# Atmega328.net
KiCad netlist of a schematic drawn in EAGLE
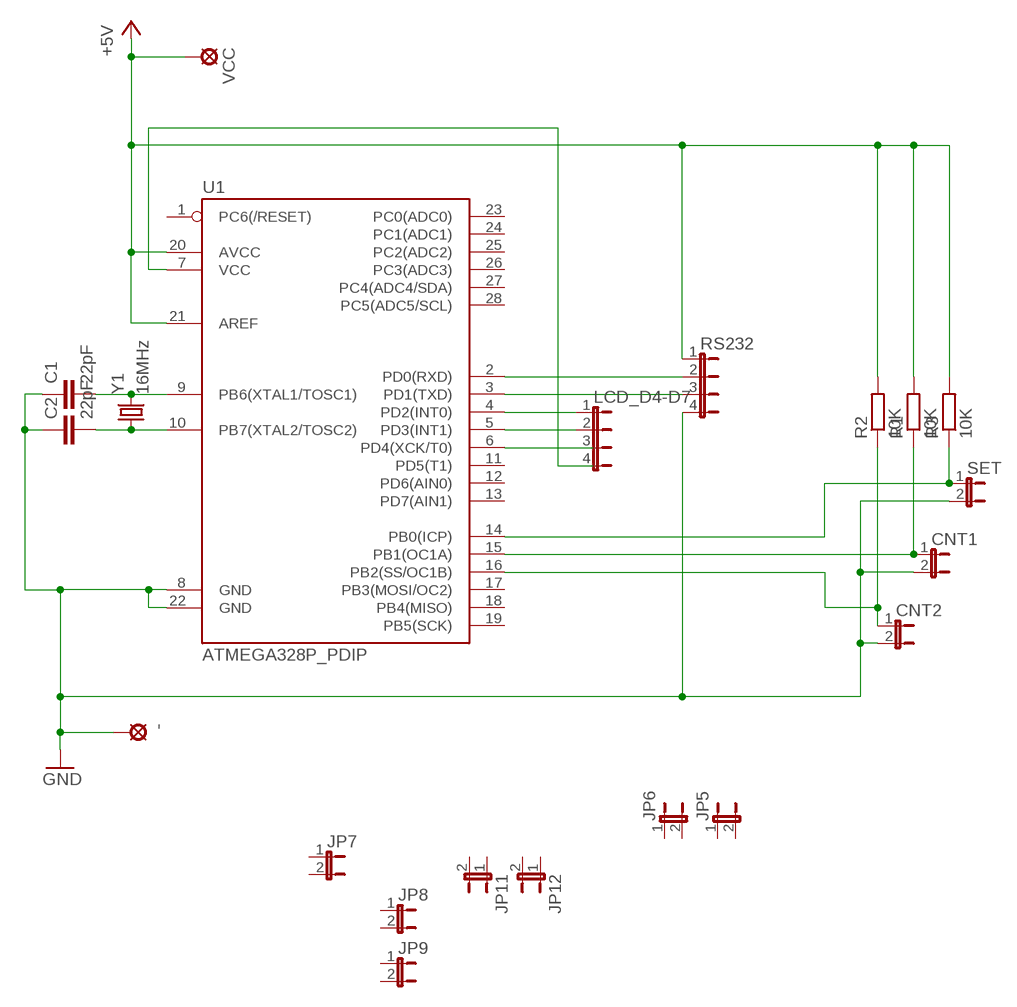
[diagram p0: schematic, sheet 1]

(export (version "E")
  (design (tool "Eeschema 10.0.6"))
  (components
    (comp (ref "-")
      (value "LSP10")
      (footprint "eagle-import:LSP10")
      (libsource (lib "eagle-import") (part "LSP10"))
    )
    (comp (ref "C1")
      (value "22pF")
      (footprint "eagle-import:C025-024X044")
      (libsource (lib "eagle-import") (part "C-EU025-024X044"))
    )
    (comp (ref "C2")
      (value "22pF")
      (footprint "eagle-import:C025-024X044")
      (libsource (lib "eagle-import") (part "C-EU025-024X044"))
    )
    (comp (ref "CNT1")
      (value "JP1E")
      (footprint "eagle-import:JP1")
      (libsource (lib "eagle-import") (part "JP1E"))
    )
    (comp (ref "CNT2")
      (value "JP1E")
      (footprint "eagle-import:JP1")
      (libsource (lib "eagle-import") (part "JP1E"))
    )
    (comp (ref "JP5")
      (value "JP1E")
      (footprint "eagle-import:JP1")
      (libsource (lib "eagle-import") (part "JP1E"))
    )
    (comp (ref "JP6")
      (value "JP1E")
      (footprint "eagle-import:JP1")
      (libsource (lib "eagle-import") (part "JP1E"))
    )
    (comp (ref "JP7")
      (value "JP1E")
      (footprint "eagle-import:JP1")
      (libsource (lib "eagle-import") (part "JP1E"))
    )
    (comp (ref "JP8")
      (value "JP1E")
      (footprint "eagle-import:JP1")
      (libsource (lib "eagle-import") (part "JP1E"))
    )
    (comp (ref "JP9")
      (value "JP1E")
      (footprint "eagle-import:JP1")
      (libsource (lib "eagle-import") (part "JP1E"))
    )
    (comp (ref "JP11")
      (value "JP1E")
      (footprint "eagle-import:JP1")
      (libsource (lib "eagle-import") (part "JP1E"))
    )
    (comp (ref "JP12")
      (value "JP1E")
      (footprint "eagle-import:JP1")
      (libsource (lib "eagle-import") (part "JP1E"))
    )
    (comp (ref "LCD_D4-D7")
      (value "JP4E")
      (footprint "eagle-import:JP4")
      (libsource (lib "eagle-import") (part "JP4E"))
    )
    (comp (ref "R1")
      (value "10K")
      (footprint "eagle-import:0204_7")
      (libsource (lib "eagle-import") (part "R-EU_0204/7"))
    )
    (comp (ref "R2")
      (value "10K")
      (footprint "eagle-import:0204_7")
      (libsource (lib "eagle-import") (part "R-EU_0204/7"))
    )
    (comp (ref "R3")
      (value "10K")
      (footprint "eagle-import:0204_7")
      (libsource (lib "eagle-import") (part "R-EU_0204/7"))
    )
    (comp (ref "RS232")
      (value "JP4E")
      (footprint "eagle-import:JP4")
      (libsource (lib "eagle-import") (part "JP4E"))
    )
    (comp (ref "SET")
      (value "JP1E")
      (footprint "eagle-import:JP1")
      (libsource (lib "eagle-import") (part "JP1E"))
    )
    (comp (ref "U1")
      (value "ATMEGA328P_PDIP")
      (footprint "eagle-import:DIL28-3")
      (libsource (lib "eagle-import") (part "ATMEGA328P_PDIP"))
    )
    (comp (ref "VCC")
      (value "LSP10")
      (footprint "eagle-import:LSP10")
      (libsource (lib "eagle-import") (part "LSP10"))
    )
    (comp (ref "Y1")
      (value "16MHz")
      (footprint "eagle-import:HC49US")
      (libsource (lib "eagle-import") (part "CRYSTALHC49US"))
    )
  )
  (nets
    (net (code "1") (name "+5V") (class "Default")
      (node (ref "R1") (pin "2") (pinfunction "2_2") (pintype "passive"))
      (node (ref "R2") (pin "2") (pinfunction "2_2") (pintype "passive"))
      (node (ref "R3") (pin "2") (pinfunction "2_2") (pintype "passive"))
      (node (ref "RS232") (pin "1") (pinfunction "1_1") (pintype "passive"))
      (node (ref "U1") (pin "20") (pinfunction "AVCC_20") (pintype "bidirectional"))
      (node (ref "U1") (pin "21") (pinfunction "AREF_21") (pintype "bidirectional"))
      (node (ref "VCC") (pin "MP") (pinfunction "MP_MP") (pintype "passive"))
    )
    (net (code "2") (name "GND") (class "Default")
      (node (ref "-") (pin "MP") (pinfunction "MP_MP") (pintype "passive"))
      (node (ref "C1") (pin "1") (pinfunction "1_1") (pintype "passive"))
      (node (ref "C2") (pin "1") (pinfunction "1_1") (pintype "passive"))
      (node (ref "CNT1") (pin "2") (pinfunction "2_2") (pintype "passive"))
      (node (ref "CNT2") (pin "2") (pinfunction "2_2") (pintype "passive"))
      (node (ref "RS232") (pin "4") (pinfunction "4_4") (pintype "passive"))
      (node (ref "SET") (pin "2") (pinfunction "2_2") (pintype "passive"))
      (node (ref "U1") (pin "22") (pinfunction "GND_22") (pintype "bidirectional"))
      (node (ref "U1") (pin "8") (pinfunction "GND_8") (pintype "bidirectional"))
    )
    (net (code "3") (name "Net-(U1-PB0(ICP))") (class "Default")
      (node (ref "R3") (pin "1") (pinfunction "1_1") (pintype "passive"))
      (node (ref "SET") (pin "1") (pinfunction "1_1") (pintype "passive"))
      (node (ref "U1") (pin "14") (pinfunction "PB0(ICP)_14") (pintype "bidirectional"))
    )
    (net (code "4") (name "Net-(U1-PB1(OC1A))") (class "Default")
      (node (ref "CNT1") (pin "1") (pinfunction "1_1") (pintype "passive"))
      (node (ref "R1") (pin "1") (pinfunction "1_1") (pintype "passive"))
      (node (ref "U1") (pin "15") (pinfunction "PB1(OC1A)_15") (pintype "bidirectional"))
    )
    (net (code "5") (name "Net-(U1-PB2(SS{slash}OC1B))") (class "Default")
      (node (ref "CNT2") (pin "1") (pinfunction "1_1") (pintype "passive"))
      (node (ref "R2") (pin "1") (pinfunction "1_1") (pintype "passive"))
      (node (ref "U1") (pin "16") (pinfunction "PB2(SS/OC1B)_16") (pintype "bidirectional"))
    )
    (net (code "6") (name "Net-(U1-PB6(XTAL1{slash}TOSC1))") (class "Default")
      (node (ref "C1") (pin "2") (pinfunction "2_2") (pintype "passive"))
      (node (ref "U1") (pin "9") (pinfunction "PB6(XTAL1/TOSC1)_9") (pintype "bidirectional"))
      (node (ref "Y1") (pin "2") (pinfunction "2_2") (pintype "passive"))
    )
    (net (code "7") (name "Net-(U1-PB7(XTAL2{slash}TOSC2))") (class "Default")
      (node (ref "C2") (pin "2") (pinfunction "2_2") (pintype "passive"))
      (node (ref "U1") (pin "10") (pinfunction "PB7(XTAL2/TOSC2)_10") (pintype "bidirectional"))
      (node (ref "Y1") (pin "1") (pinfunction "1_1") (pintype "passive"))
    )
    (net (code "8") (name "Net-(U1-PD0(RXD))") (class "Default")
      (node (ref "RS232") (pin "2") (pinfunction "2_2") (pintype "passive"))
      (node (ref "U1") (pin "2") (pinfunction "PD0(RXD)_2") (pintype "bidirectional"))
    )
    (net (code "9") (name "Net-(U1-PD1(TXD))") (class "Default")
      (node (ref "RS232") (pin "3") (pinfunction "3_3") (pintype "passive"))
      (node (ref "U1") (pin "3") (pinfunction "PD1(TXD)_3") (pintype "bidirectional"))
    )
    (net (code "10") (name "Net-(U1-PD2(INT0))") (class "Default")
      (node (ref "LCD_D4-D7") (pin "1") (pinfunction "1_1") (pintype "passive"))
      (node (ref "U1") (pin "4") (pinfunction "PD2(INT0)_4") (pintype "bidirectional"))
    )
    (net (code "11") (name "Net-(U1-PD3(INT1))") (class "Default")
      (node (ref "LCD_D4-D7") (pin "2") (pinfunction "2_2") (pintype "passive"))
      (node (ref "U1") (pin "5") (pinfunction "PD3(INT1)_5") (pintype "bidirectional"))
    )
    (net (code "12") (name "unconnected-(JP5-Pad1)") (class "Default")
      (node (ref "JP5") (pin "1") (pinfunction "1_1") (pintype "passive"))
    )
    (net (code "13") (name "unconnected-(JP5-Pad2)") (class "Default")
      (node (ref "JP5") (pin "2") (pinfunction "2_2") (pintype "passive"))
    )
    (net (code "14") (name "unconnected-(JP6-Pad1)") (class "Default")
      (node (ref "JP6") (pin "1") (pinfunction "1_1") (pintype "passive"))
    )
    (net (code "15") (name "unconnected-(JP6-Pad2)") (class "Default")
      (node (ref "JP6") (pin "2") (pinfunction "2_2") (pintype "passive"))
    )
    (net (code "16") (name "unconnected-(JP7-Pad1)") (class "Default")
      (node (ref "JP7") (pin "1") (pinfunction "1_1") (pintype "passive"))
    )
    (net (code "17") (name "unconnected-(JP7-Pad2)") (class "Default")
      (node (ref "JP7") (pin "2") (pinfunction "2_2") (pintype "passive"))
    )
    (net (code "18") (name "unconnected-(JP8-Pad1)") (class "Default")
      (node (ref "JP8") (pin "1") (pinfunction "1_1") (pintype "passive"))
    )
    (net (code "19") (name "unconnected-(JP8-Pad2)") (class "Default")
      (node (ref "JP8") (pin "2") (pinfunction "2_2") (pintype "passive"))
    )
    (net (code "20") (name "unconnected-(JP9-Pad1)") (class "Default")
      (node (ref "JP9") (pin "1") (pinfunction "1_1") (pintype "passive"))
    )
    (net (code "21") (name "unconnected-(JP9-Pad2)") (class "Default")
      (node (ref "JP9") (pin "2") (pinfunction "2_2") (pintype "passive"))
    )
    (net (code "22") (name "unconnected-(JP11-Pad1)") (class "Default")
      (node (ref "JP11") (pin "1") (pinfunction "1_1") (pintype "passive"))
    )
    (net (code "23") (name "unconnected-(JP11-Pad2)") (class "Default")
      (node (ref "JP11") (pin "2") (pinfunction "2_2") (pintype "passive"))
    )
    (net (code "24") (name "unconnected-(JP12-Pad1)") (class "Default")
      (node (ref "JP12") (pin "1") (pinfunction "1_1") (pintype "passive"))
    )
    (net (code "25") (name "unconnected-(JP12-Pad2)") (class "Default")
      (node (ref "JP12") (pin "2") (pinfunction "2_2") (pintype "passive"))
    )
    (net (code "26") (name "unconnected-(LCD_D4-D7-Pad3)") (class "Default")
      (node (ref "LCD_D4-D7") (pin "3") (pinfunction "3_3") (pintype "passive"))
    )
    (net (code "27") (name "unconnected-(LCD_D4-D7-Pad4)") (class "Default")
      (node (ref "LCD_D4-D7") (pin "4") (pinfunction "4_4") (pintype "passive"))
    )
    (net (code "28") (name "unconnected-(U1-PB3(MOSI{slash}OC2)-Pad17)") (class "Default")
      (node (ref "U1") (pin "17") (pinfunction "PB3(MOSI/OC2)_17") (pintype "bidirectional"))
    )
    (net (code "29") (name "unconnected-(U1-PB4(MISO)-Pad18)") (class "Default")
      (node (ref "U1") (pin "18") (pinfunction "PB4(MISO)_18") (pintype "bidirectional"))
    )
    (net (code "30") (name "unconnected-(U1-PB5(SCK)-Pad19)") (class "Default")
      (node (ref "U1") (pin "19") (pinfunction "PB5(SCK)_19") (pintype "bidirectional"))
    )
    (net (code "31") (name "unconnected-(U1-PC0(ADC0)-Pad23)") (class "Default")
      (node (ref "U1") (pin "23") (pinfunction "PC0(ADC0)_23") (pintype "bidirectional"))
    )
    (net (code "32") (name "unconnected-(U1-PC1(ADC1)-Pad24)") (class "Default")
      (node (ref "U1") (pin "24") (pinfunction "PC1(ADC1)_24") (pintype "bidirectional"))
    )
    (net (code "33") (name "unconnected-(U1-PC2(ADC2)-Pad25)") (class "Default")
      (node (ref "U1") (pin "25") (pinfunction "PC2(ADC2)_25") (pintype "bidirectional"))
    )
    (net (code "34") (name "unconnected-(U1-PC3(ADC3)-Pad26)") (class "Default")
      (node (ref "U1") (pin "26") (pinfunction "PC3(ADC3)_26") (pintype "bidirectional"))
    )
    (net (code "35") (name "unconnected-(U1-PC4(ADC4{slash}SDA)-Pad27)") (class "Default")
      (node (ref "U1") (pin "27") (pinfunction "PC4(ADC4/SDA)_27") (pintype "bidirectional"))
    )
    (net (code "36") (name "unconnected-(U1-PC5(ADC5{slash}SCL)-Pad28)") (class "Default")
      (node (ref "U1") (pin "28") (pinfunction "PC5(ADC5/SCL)_28") (pintype "bidirectional"))
    )
    (net (code "37") (name "unconnected-(U1-PC6({slash}RESET)-Pad1)") (class "Default")
      (node (ref "U1") (pin "1") (pinfunction "PC6(/RESET)_1") (pintype "bidirectional"))
    )
    (net (code "38") (name "unconnected-(U1-PD4(XCK{slash}T0)-Pad6)") (class "Default")
      (node (ref "U1") (pin "6") (pinfunction "PD4(XCK/T0)_6") (pintype "bidirectional"))
    )
    (net (code "39") (name "unconnected-(U1-PD5(T1)-Pad11)") (class "Default")
      (node (ref "U1") (pin "11") (pinfunction "PD5(T1)_11") (pintype "bidirectional"))
    )
    (net (code "40") (name "unconnected-(U1-PD6(AIN0)-Pad12)") (class "Default")
      (node (ref "U1") (pin "12") (pinfunction "PD6(AIN0)_12") (pintype "bidirectional"))
    )
    (net (code "41") (name "unconnected-(U1-PD7(AIN1)-Pad13)") (class "Default")
      (node (ref "U1") (pin "13") (pinfunction "PD7(AIN1)_13") (pintype "bidirectional"))
    )
    (net (code "42") (name "unconnected-(U1-VCC-Pad7)") (class "Default")
      (node (ref "U1") (pin "7") (pinfunction "VCC_7") (pintype "bidirectional"))
    )
  )
)
